# IO_Carte_Nucleo2.net
KiCad netlist of a schematic drawn in Altium Designer
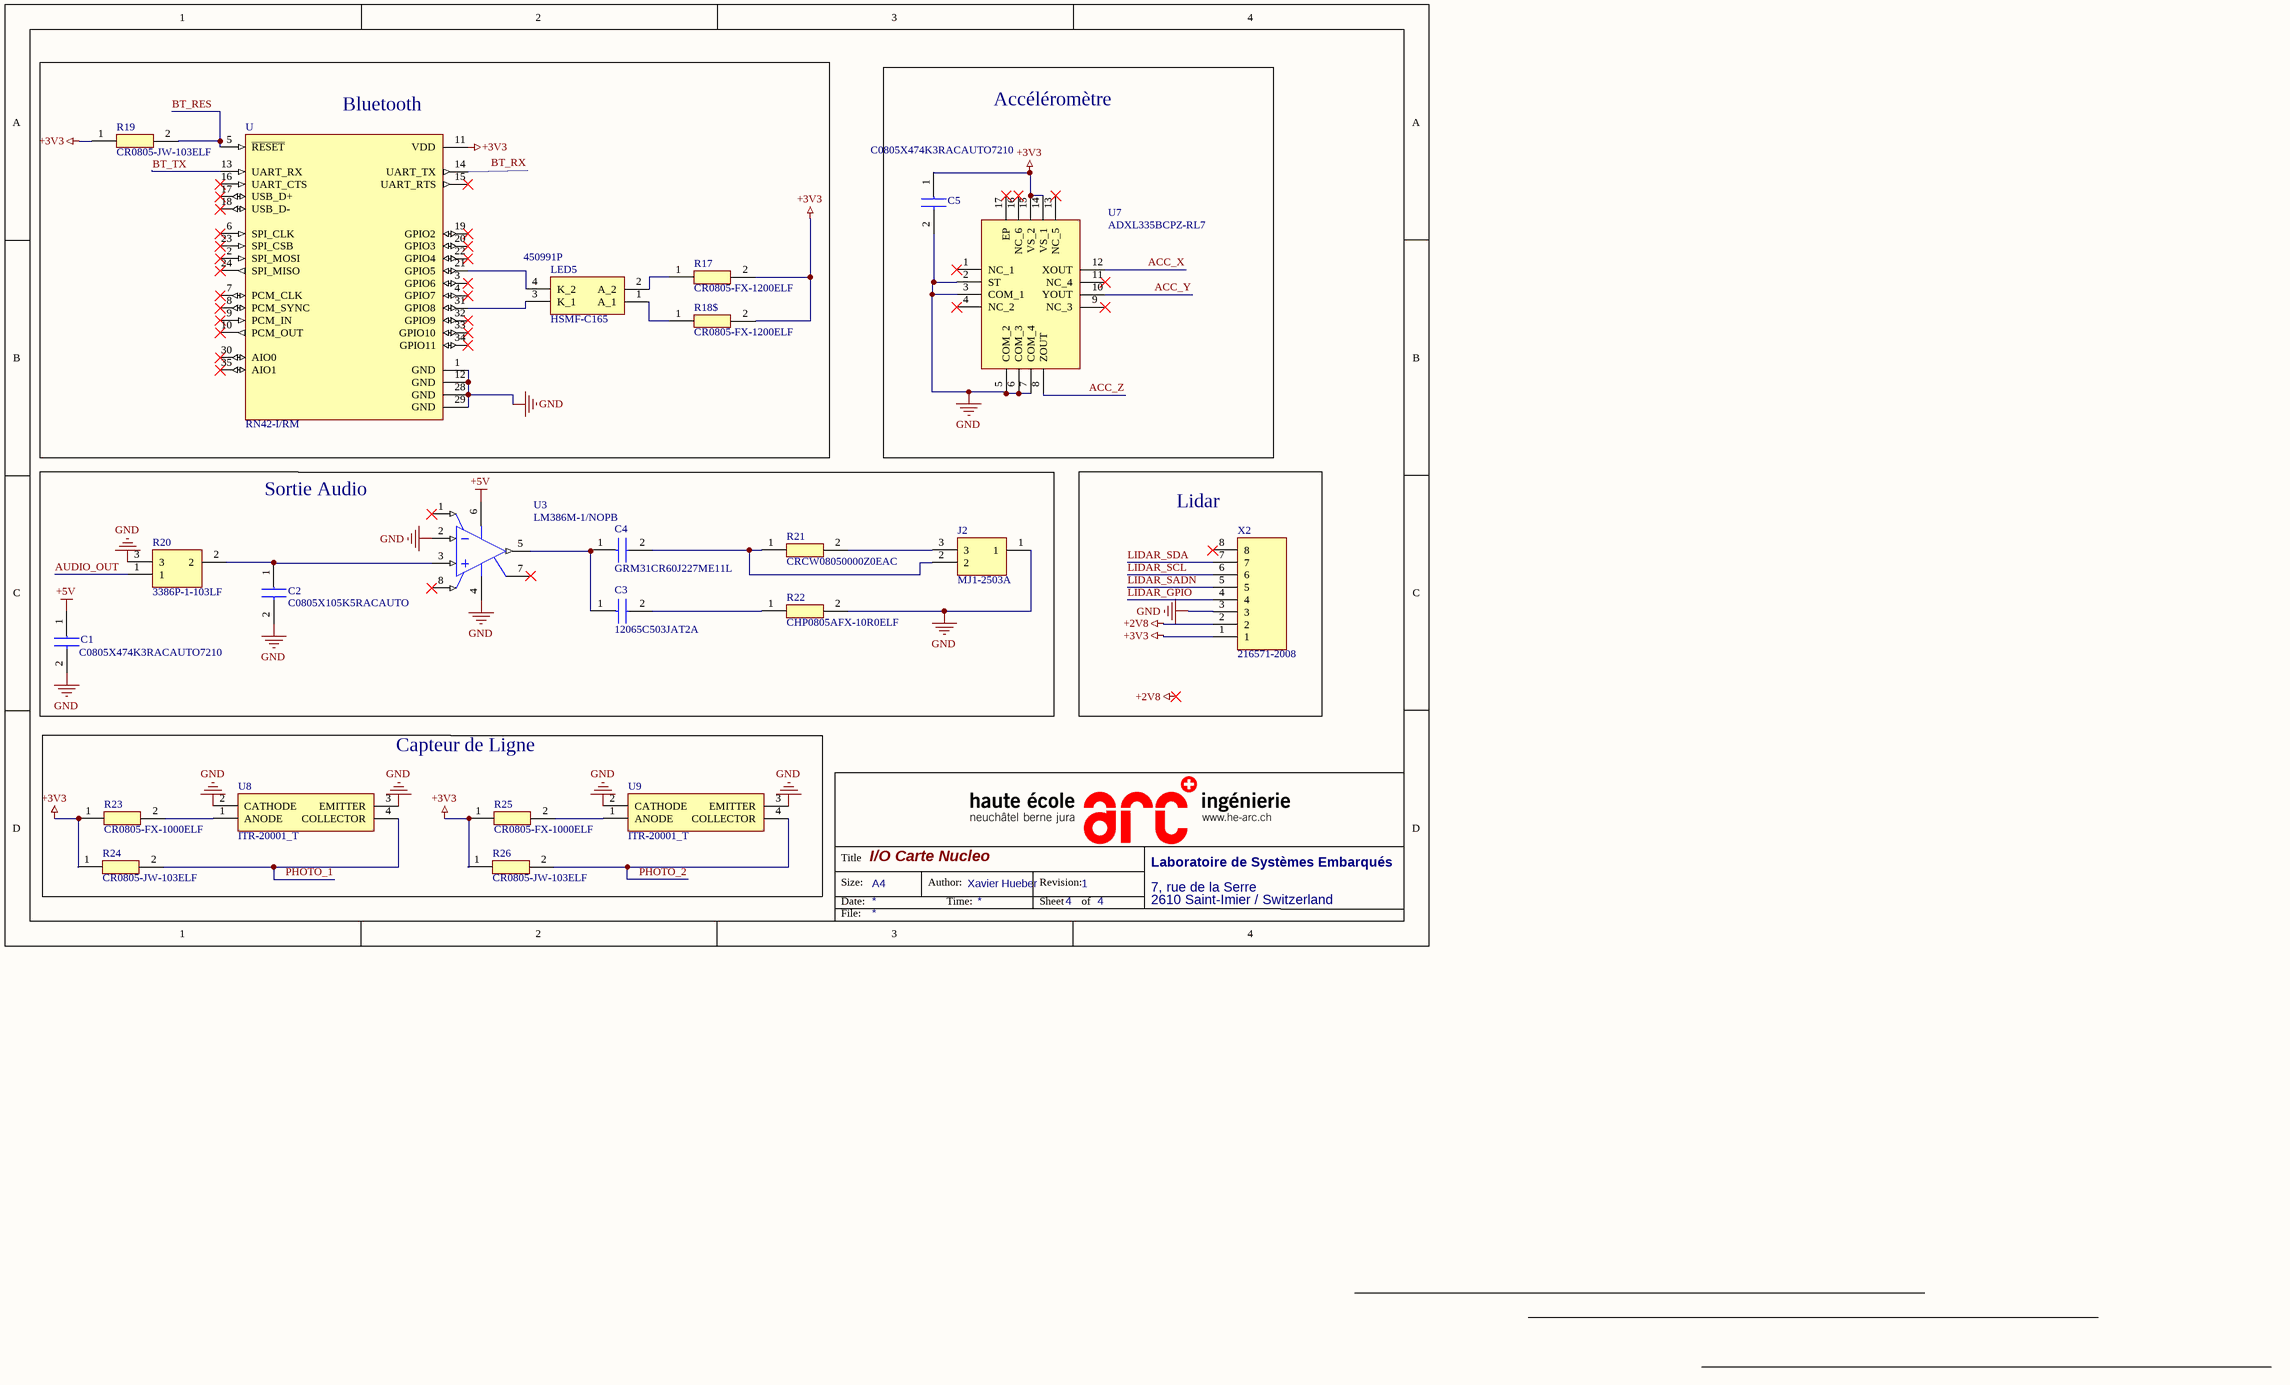
[diagram p0: IO_Carte_Nucleo2_.SchDoc]

(export (version "E")
  (design (tool "Eeschema 10.0.6"))
  (components
    (comp (ref "C1")
      (value "C0805X474K3RACAUTO7210")
      (footprint "SamacSys:C0805")
      (description "Capacitor")
      (libsource (lib "*") (part "C0805X474K3RACAUTO7210"))
    )
    (comp (ref "C2")
      (value "C0805X105K5RACAUTO")
      (footprint "SamacSys:CAPC2012X145N")
      (description "Capacitor")
      (libsource (lib "*") (part "C0805X105K5RACAUTO"))
    )
    (comp (ref "C3")
      (value "12065C503JAT2A")
      (footprint "SamacSys:CAPC3216X94N")
      (description "Capacitor")
      (libsource (lib "*") (part "12065C503JAT2A"))
    )
    (comp (ref "C4")
      (value "GRM31CR60J227ME11L")
      (footprint "SamacSys:CAPC3216X190N")
      (description "Capacitor")
      (libsource (lib "*") (part "GRM31CR60J227ME11L"))
    )
    (comp (ref "C5")
      (value "C0805X474K3RACAUTO7210")
      (footprint "SamacSys:C0805")
      (description "Capacitor")
      (libsource (lib "*") (part "C0805X474K3RACAUTO7210"))
    )
    (comp (ref "J2")
      (value "MJ1-2503A")
      (footprint "SamacSys:MJ12503A")
      (description "Connector")
      (fields (field (name "MOUSER2 PART NUMBER") "490-MJ1-2503A"))
      (libsource (lib "*") (part "MJ1-2503A"))
    )
    (comp (ref "LED5")
      (value "HSMF-C165")
      (footprint "SamacSys:HSMF-C163")
      (description "LED Bi-Color Green/Red 570nm/636nm 4-Pin Chip 0603 T/R")
      (fields
        (field (name "MOUSER2 PART NUMBER") "630-HSMF-C165")
        (field (name "SUPPLIER PART NUMBER 1") "450991P")
      )
      (libsource (lib "*") (part "HSMF-C165"))
    )
    (comp (ref "R17")
      (value "CR0805-FX-1200ELF")
      (footprint "SamacSys:RESC2012X60N")
      (description "Resistor")
      (libsource (lib "*") (part "CR0805-FX-1200ELF"))
    )
    (comp (ref "R18$")
      (value "CR0805-FX-1200ELF")
      (footprint "SamacSys:RESC2012X60N")
      (description "Resistor")
      (libsource (lib "*") (part "CR0805-FX-1200ELF"))
    )
    (comp (ref "R19")
      (value "CR0805-JW-103ELF")
      (footprint "SamacSys:RESC2012X60N")
      (libsource (lib "*") (part "CR0805-JW-103ELF"))
    )
    (comp (ref "R20")
      (value "3386P-1-103LF")
      (footprint "SamacSys:3386P_1")
      (description "Resistor")
      (fields (field (name "MOUSER2 PART NUMBER") "652-3386P-1-103LF"))
      (libsource (lib "*") (part "3386P-1-103LF"))
    )
    (comp (ref "R21")
      (value "CRCW08050000Z0EAC")
      (footprint "SamacSys:RESC2012X60N")
      (description "Resistor")
      (fields (field (name "MOUSER2 PART NUMBER") "71-CRCW08050000Z0EAC"))
      (libsource (lib "*") (part "CRCW08050000Z0EAC"))
    )
    (comp (ref "R22")
      (value "CHP0805AFX-10R0ELF")
      (footprint "SamacSys:RESC2012X60N")
      (description "Resistor")
      (libsource (lib "*") (part "CHP0805AFX-10R0ELF"))
    )
    (comp (ref "R23")
      (value "CR0805-FX-1000ELF")
      (footprint "SamacSys:RESC2012X60N")
      (description "Resistor")
      (libsource (lib "*") (part "CR0805-FX-1000ELF"))
    )
    (comp (ref "R24")
      (value "CR0805-JW-103ELF")
      (footprint "SamacSys:RESC2012X60N")
      (description "Resistor")
      (fields (field (name "MOUSER2 PART NUMBER") "652-CR0805-JW-103ELF"))
      (libsource (lib "*") (part "CR0805-JW-103ELF"))
    )
    (comp (ref "R25")
      (value "CR0805-FX-1000ELF")
      (footprint "SamacSys:RESC2012X60N")
      (description "Resistor")
      (libsource (lib "*") (part "CR0805-FX-1000ELF"))
    )
    (comp (ref "R26")
      (value "CR0805-JW-103ELF")
      (footprint "SamacSys:RESC2012X60N")
      (description "Resistor")
      (fields (field (name "MOUSER2 PART NUMBER") "652-CR0805-JW-103ELF"))
      (libsource (lib "*") (part "CR0805-JW-103ELF"))
    )
    (comp (ref "U")
      (value "RN42-I/RM")
      (footprint "SnapEDApcb:XCVR_RN42-I/RM")
      (description "Bluetooth Bluetooth v2.1 +EDR, Class 2 Transceiver Module 2.4GHz Integrated, Trace Surface Mount")
      (fields (field (name "MF") "Microchip"))
      (libsource (lib "SnapEDAsch") (part "RN42-I/RM"))
    )
    (comp (ref "U3")
      (value "LM386M-1/NOPB")
      (footprint "TI-D8_M")
      (description "Low Voltage Audio Power Amplifier, 0 to 70 degC, 8-pin SOIC (D8), Green (RoHS & no Sb/Br)")
      (fields (field (name "MANUFACTURER") "Texas Instruments"))
      (libsource (lib "Altium Content Vault") (part "TI-LM386undefined"))
    )
    (comp (ref "U7")
      (value "ADXL335BCPZ-RL7")
      (footprint "SamacSys:QFN65P400X400X150-17N-D")
      (description "Integrated Circuit")
      (fields (field (name "MOUSER2 PART NUMBER") "584-ADXL335BCPZ-R7"))
      (libsource (lib "*") (part "ADXL335BCPZ-RL7"))
    )
    (comp (ref "U8")
      (value "ITR-20001_T")
      (footprint "SamacSys:ITR20001T")
      (description "Undefined or Miscellaneous")
      (fields (field (name "MANUFACTURER_PART_NUMBER") "ITR-20001/T"))
      (libsource (lib "*") (part "ITR-20001_T"))
    )
    (comp (ref "U9")
      (value "ITR-20001_T")
      (footprint "SamacSys:ITR20001T")
      (description "Undefined or Miscellaneous")
      (fields (field (name "MANUFACTURER_PART_NUMBER") "ITR-20001/T"))
      (libsource (lib "*") (part "ITR-20001_T"))
    )
    (comp (ref "X2")
      (value "216571-2008")
      (footprint "SamacSys:216571-YY08")
      (description "Connector")
      (libsource (lib "*") (part "216571-2008"))
    )
  )
  (nets
    (net (code "1") (name "+2V8") (class "Default")
      (node (ref "X2") (pin "2") (pinfunction "2_2") (pintype "passive"))
    )
    (net (code "2") (name "+3V3") (class "Default")
      (node (ref "C5") (pin "1") (pinfunction "1_1") (pintype "passive"))
      (node (ref "R17") (pin "2") (pinfunction "2_2") (pintype "passive"))
      (node (ref "R18$") (pin "2") (pinfunction "2_2") (pintype "passive"))
      (node (ref "R19") (pin "1") (pinfunction "1_1") (pintype "passive"))
      (node (ref "R23") (pin "1") (pinfunction "1_1") (pintype "passive"))
      (node (ref "R24") (pin "1") (pinfunction "1_1") (pintype "passive"))
      (node (ref "R25") (pin "1") (pinfunction "1_1") (pintype "passive"))
      (node (ref "R26") (pin "1") (pinfunction "1_1") (pintype "passive"))
      (node (ref "U") (pin "11") (pinfunction "VDD_11") (pintype "power_in"))
      (node (ref "U7") (pin "14") (pinfunction "VS_1_14") (pintype "passive"))
      (node (ref "U7") (pin "15") (pinfunction "VS_2_15") (pintype "passive"))
      (node (ref "X2") (pin "1") (pinfunction "1_1") (pintype "passive"))
    )
    (net (code "3") (name "+5V") (class "Default")
      (node (ref "C1") (pin "1") (pinfunction "1_1") (pintype "passive"))
      (node (ref "U3") (pin "6") (pinfunction "VS_6") (pintype "power_in"))
    )
    (net (code "4") (name "/ACC_X") (class "Default")
      (node (ref "U7") (pin "12") (pinfunction "XOUT_12") (pintype "passive"))
    )
    (net (code "5") (name "/ACC_Y") (class "Default")
      (node (ref "U7") (pin "10") (pinfunction "YOUT_10") (pintype "passive"))
    )
    (net (code "6") (name "/ACC_Z") (class "Default")
      (node (ref "U7") (pin "8") (pinfunction "ZOUT_8") (pintype "passive"))
    )
    (net (code "7") (name "/AUDIO_OUT") (class "Default")
      (node (ref "R20") (pin "1") (pinfunction "1_1") (pintype "passive"))
    )
    (net (code "8") (name "/BT_RES") (class "Default")
      (node (ref "R19") (pin "2") (pinfunction "2_2") (pintype "passive"))
      (node (ref "U") (pin "5") (pinfunction "~{RESET}_5") (pintype "input"))
    )
    (net (code "9") (name "/BT_RX") (class "Default")
      (node (ref "U") (pin "14") (pinfunction "UART_TX_14") (pintype "output"))
    )
    (net (code "10") (name "/BT_TX") (class "Default")
      (node (ref "U") (pin "13") (pinfunction "UART_RX_13") (pintype "input"))
    )
    (net (code "11") (name "/LIDAR_GPIO") (class "Default")
      (node (ref "X2") (pin "4") (pinfunction "4_4") (pintype "passive"))
    )
    (net (code "12") (name "/LIDAR_SADN") (class "Default")
      (node (ref "X2") (pin "5") (pinfunction "5_5") (pintype "passive"))
    )
    (net (code "13") (name "/LIDAR_SCL") (class "Default")
      (node (ref "X2") (pin "6") (pinfunction "6_6") (pintype "passive"))
    )
    (net (code "14") (name "/LIDAR_SDA") (class "Default")
      (node (ref "X2") (pin "7") (pinfunction "7_7") (pintype "passive"))
    )
    (net (code "15") (name "/PHOTO_1") (class "Default")
      (node (ref "R24") (pin "2") (pinfunction "2_2") (pintype "passive"))
      (node (ref "U8") (pin "4") (pinfunction "COLLECTOR_4") (pintype "passive"))
    )
    (net (code "16") (name "/PHOTO_2") (class "Default")
      (node (ref "R26") (pin "2") (pinfunction "2_2") (pintype "passive"))
      (node (ref "U9") (pin "4") (pinfunction "COLLECTOR_4") (pintype "passive"))
    )
    (net (code "17") (name "GND") (class "Default")
      (node (ref "C1") (pin "2") (pinfunction "2_2") (pintype "passive"))
      (node (ref "C2") (pin "2") (pinfunction "2_2") (pintype "passive"))
      (node (ref "C5") (pin "2") (pinfunction "2_2") (pintype "passive"))
      (node (ref "J2") (pin "1") (pinfunction "1_1") (pintype "passive"))
      (node (ref "R20") (pin "3") (pinfunction "3_3") (pintype "passive"))
      (node (ref "R22") (pin "2") (pinfunction "2_2") (pintype "passive"))
      (node (ref "U") (pin "1") (pinfunction "GND_1") (pintype "power_in"))
      (node (ref "U") (pin "12") (pinfunction "GND_12") (pintype "power_in"))
      (node (ref "U") (pin "28") (pinfunction "GND_28") (pintype "power_in"))
      (node (ref "U") (pin "29") (pinfunction "GND_29") (pintype "power_in"))
      (node (ref "U3") (pin "2") (pinfunction "IN-_2") (pintype "input"))
      (node (ref "U3") (pin "4") (pinfunction "GND_4") (pintype "power_in"))
      (node (ref "U7") (pin "2") (pinfunction "ST_2") (pintype "passive"))
      (node (ref "U7") (pin "3") (pinfunction "COM_1_3") (pintype "passive"))
      (node (ref "U7") (pin "5") (pinfunction "COM_2_5") (pintype "passive"))
      (node (ref "U7") (pin "6") (pinfunction "COM_3_6") (pintype "passive"))
      (node (ref "U7") (pin "7") (pinfunction "COM_4_7") (pintype "passive"))
      (node (ref "U8") (pin "2") (pinfunction "CATHODE_2") (pintype "passive"))
      (node (ref "U8") (pin "3") (pinfunction "EMITTER_3") (pintype "passive"))
      (node (ref "U9") (pin "2") (pinfunction "CATHODE_2") (pintype "passive"))
      (node (ref "U9") (pin "3") (pinfunction "EMITTER_3") (pintype "passive"))
      (node (ref "X2") (pin "3") (pinfunction "3_3") (pintype "passive"))
    )
    (net (code "18") (name "Net-(C3-C1)") (class "Default")
      (node (ref "C3") (pin "1") (pinfunction "C1_1") (pintype "passive"))
      (node (ref "C4") (pin "1") (pinfunction "1_1") (pintype "passive"))
      (node (ref "U3") (pin "5") (pinfunction "VOUT_5") (pintype "output"))
    )
    (net (code "19") (name "Net-(C3-C2)") (class "Default")
      (node (ref "C3") (pin "2") (pinfunction "C2_2") (pintype "passive"))
      (node (ref "R22") (pin "1") (pinfunction "1_1") (pintype "passive"))
    )
    (net (code "20") (name "Net-(C4-Pad2)") (class "Default")
      (node (ref "C4") (pin "2") (pinfunction "2_2") (pintype "passive"))
      (node (ref "J2") (pin "2") (pinfunction "2_2") (pintype "passive"))
      (node (ref "R21") (pin "1") (pinfunction "1_1") (pintype "passive"))
    )
    (net (code "21") (name "Net-(J2-Pad3)") (class "Default")
      (node (ref "J2") (pin "3") (pinfunction "3_3") (pintype "passive"))
      (node (ref "R21") (pin "2") (pinfunction "2_2") (pintype "passive"))
    )
    (net (code "22") (name "Net-(LED5-A_1)") (class "Default")
      (node (ref "LED5") (pin "1") (pinfunction "A_1_1") (pintype "passive"))
      (node (ref "R18$") (pin "1") (pinfunction "1_1") (pintype "passive"))
    )
    (net (code "23") (name "Net-(LED5-A_2)") (class "Default")
      (node (ref "LED5") (pin "2") (pinfunction "A_2_2") (pintype "passive"))
      (node (ref "R17") (pin "1") (pinfunction "1_1") (pintype "passive"))
    )
    (net (code "24") (name "Net-(LED5-K_1)") (class "Default")
      (node (ref "LED5") (pin "3") (pinfunction "K_1_3") (pintype "passive"))
      (node (ref "U") (pin "31") (pinfunction "GPIO8_31") (pintype "bidirectional"))
    )
    (net (code "25") (name "Net-(LED5-K_2)") (class "Default")
      (node (ref "LED5") (pin "4") (pinfunction "K_2_4") (pintype "passive"))
      (node (ref "U") (pin "21") (pinfunction "GPIO5_21") (pintype "bidirectional"))
    )
    (net (code "26") (name "Net-(U3-IN+)") (class "Default")
      (node (ref "C2") (pin "1") (pinfunction "1_1") (pintype "passive"))
      (node (ref "R20") (pin "2") (pinfunction "2_2") (pintype "passive"))
      (node (ref "U3") (pin "3") (pinfunction "IN+_3") (pintype "input"))
    )
    (net (code "27") (name "Net-(U8-ANODE)") (class "Default")
      (node (ref "R23") (pin "2") (pinfunction "2_2") (pintype "passive"))
      (node (ref "U8") (pin "1") (pinfunction "ANODE_1") (pintype "passive"))
    )
    (net (code "28") (name "Net-(U9-ANODE)") (class "Default")
      (node (ref "R25") (pin "2") (pinfunction "2_2") (pintype "passive"))
      (node (ref "U9") (pin "1") (pinfunction "ANODE_1") (pintype "passive"))
    )
    (net (code "29") (name "unconnected-(U-AIO0-Pad30)") (class "Default")
      (node (ref "U") (pin "30") (pinfunction "AIO0_30") (pintype "bidirectional+no_connect"))
    )
    (net (code "30") (name "unconnected-(U-AIO1-Pad35)") (class "Default")
      (node (ref "U") (pin "35") (pinfunction "AIO1_35") (pintype "bidirectional+no_connect"))
    )
    (net (code "31") (name "unconnected-(U-GPIO2-Pad19)") (class "Default")
      (node (ref "U") (pin "19") (pinfunction "GPIO2_19") (pintype "bidirectional+no_connect"))
    )
    (net (code "32") (name "unconnected-(U-GPIO3-Pad20)") (class "Default")
      (node (ref "U") (pin "20") (pinfunction "GPIO3_20") (pintype "bidirectional+no_connect"))
    )
    (net (code "33") (name "unconnected-(U-GPIO4-Pad22)") (class "Default")
      (node (ref "U") (pin "22") (pinfunction "GPIO4_22") (pintype "bidirectional+no_connect"))
    )
    (net (code "34") (name "unconnected-(U-GPIO6-Pad3)") (class "Default")
      (node (ref "U") (pin "3") (pinfunction "GPIO6_3") (pintype "bidirectional+no_connect"))
    )
    (net (code "35") (name "unconnected-(U-GPIO7-Pad4)") (class "Default")
      (node (ref "U") (pin "4") (pinfunction "GPIO7_4") (pintype "bidirectional+no_connect"))
    )
    (net (code "36") (name "unconnected-(U-GPIO9-Pad32)") (class "Default")
      (node (ref "U") (pin "32") (pinfunction "GPIO9_32") (pintype "bidirectional+no_connect"))
    )
    (net (code "37") (name "unconnected-(U-GPIO10-Pad33)") (class "Default")
      (node (ref "U") (pin "33") (pinfunction "GPIO10_33") (pintype "bidirectional+no_connect"))
    )
    (net (code "38") (name "unconnected-(U-GPIO11-Pad34)") (class "Default")
      (node (ref "U") (pin "34") (pinfunction "GPIO11_34") (pintype "bidirectional+no_connect"))
    )
    (net (code "39") (name "unconnected-(U-PCM_CLK-Pad7)") (class "Default")
      (node (ref "U") (pin "7") (pinfunction "PCM_CLK_7") (pintype "bidirectional+no_connect"))
    )
    (net (code "40") (name "unconnected-(U-PCM_IN-Pad9)") (class "Default")
      (node (ref "U") (pin "9") (pinfunction "PCM_IN_9") (pintype "input+no_connect"))
    )
    (net (code "41") (name "unconnected-(U-PCM_OUT-Pad10)") (class "Default")
      (node (ref "U") (pin "10") (pinfunction "PCM_OUT_10") (pintype "output+no_connect"))
    )
    (net (code "42") (name "unconnected-(U-PCM_SYNC-Pad8)") (class "Default")
      (node (ref "U") (pin "8") (pinfunction "PCM_SYNC_8") (pintype "bidirectional+no_connect"))
    )
    (net (code "43") (name "unconnected-(U-SPI_CLK-Pad6)") (class "Default")
      (node (ref "U") (pin "6") (pinfunction "SPI_CLK_6") (pintype "input+no_connect"))
    )
    (net (code "44") (name "unconnected-(U-SPI_CSB-Pad23)") (class "Default")
      (node (ref "U") (pin "23") (pinfunction "SPI_CSB_23") (pintype "input+no_connect"))
    )
    (net (code "45") (name "unconnected-(U-SPI_MISO-Pad24)") (class "Default")
      (node (ref "U") (pin "24") (pinfunction "SPI_MISO_24") (pintype "output+no_connect"))
    )
    (net (code "46") (name "unconnected-(U-SPI_MOSI-Pad2)") (class "Default")
      (node (ref "U") (pin "2") (pinfunction "SPI_MOSI_2") (pintype "input+no_connect"))
    )
    (net (code "47") (name "unconnected-(U-UART_CTS-Pad16)") (class "Default")
      (node (ref "U") (pin "16") (pinfunction "UART_CTS_16") (pintype "input+no_connect"))
    )
    (net (code "48") (name "unconnected-(U-UART_RTS-Pad15)") (class "Default")
      (node (ref "U") (pin "15") (pinfunction "UART_RTS_15") (pintype "output+no_connect"))
    )
    (net (code "49") (name "unconnected-(U-USB_D+-Pad17)") (class "Default")
      (node (ref "U") (pin "17") (pinfunction "USB_D+_17") (pintype "bidirectional+no_connect"))
    )
    (net (code "50") (name "unconnected-(U-USB_D--Pad18)") (class "Default")
      (node (ref "U") (pin "18") (pinfunction "USB_D-_18") (pintype "bidirectional+no_connect"))
    )
    (net (code "51") (name "unconnected-(U3-BYPASS-Pad7)") (class "Default")
      (node (ref "U3") (pin "7") (pinfunction "BYPASS_7") (pintype "passive+no_connect"))
    )
    (net (code "52") (name "unconnected-(U3-GAIN-Pad1)") (class "Default")
      (node (ref "U3") (pin "1") (pinfunction "GAIN_1") (pintype "input+no_connect"))
    )
    (net (code "53") (name "unconnected-(U3-GAIN-Pad8)") (class "Default")
      (node (ref "U3") (pin "8") (pinfunction "GAIN_8") (pintype "input+no_connect"))
    )
    (net (code "54") (name "unconnected-(U7-EP-Pad17)") (class "Default")
      (node (ref "U7") (pin "17") (pinfunction "EP_17") (pintype "passive+no_connect"))
    )
    (net (code "55") (name "unconnected-(U7-NC_1-Pad1)") (class "Default")
      (node (ref "U7") (pin "1") (pinfunction "NC_1_1") (pintype "passive+no_connect"))
    )
    (net (code "56") (name "unconnected-(U7-NC_2-Pad4)") (class "Default")
      (node (ref "U7") (pin "4") (pinfunction "NC_2_4") (pintype "passive+no_connect"))
    )
    (net (code "57") (name "unconnected-(U7-NC_3-Pad9)") (class "Default")
      (node (ref "U7") (pin "9") (pinfunction "NC_3_9") (pintype "passive+no_connect"))
    )
    (net (code "58") (name "unconnected-(U7-NC_4-Pad11)") (class "Default")
      (node (ref "U7") (pin "11") (pinfunction "NC_4_11") (pintype "passive+no_connect"))
    )
    (net (code "59") (name "unconnected-(U7-NC_5-Pad13)") (class "Default")
      (node (ref "U7") (pin "13") (pinfunction "NC_5_13") (pintype "passive+no_connect"))
    )
    (net (code "60") (name "unconnected-(U7-NC_6-Pad16)") (class "Default")
      (node (ref "U7") (pin "16") (pinfunction "NC_6_16") (pintype "passive+no_connect"))
    )
    (net (code "61") (name "unconnected-(X2-Pad8)") (class "Default")
      (node (ref "X2") (pin "8") (pinfunction "8_8") (pintype "passive+no_connect"))
    )
  )
)
